# GL3520_4_Ports.net
KiCad netlist of a schematic drawn in Altium Designer
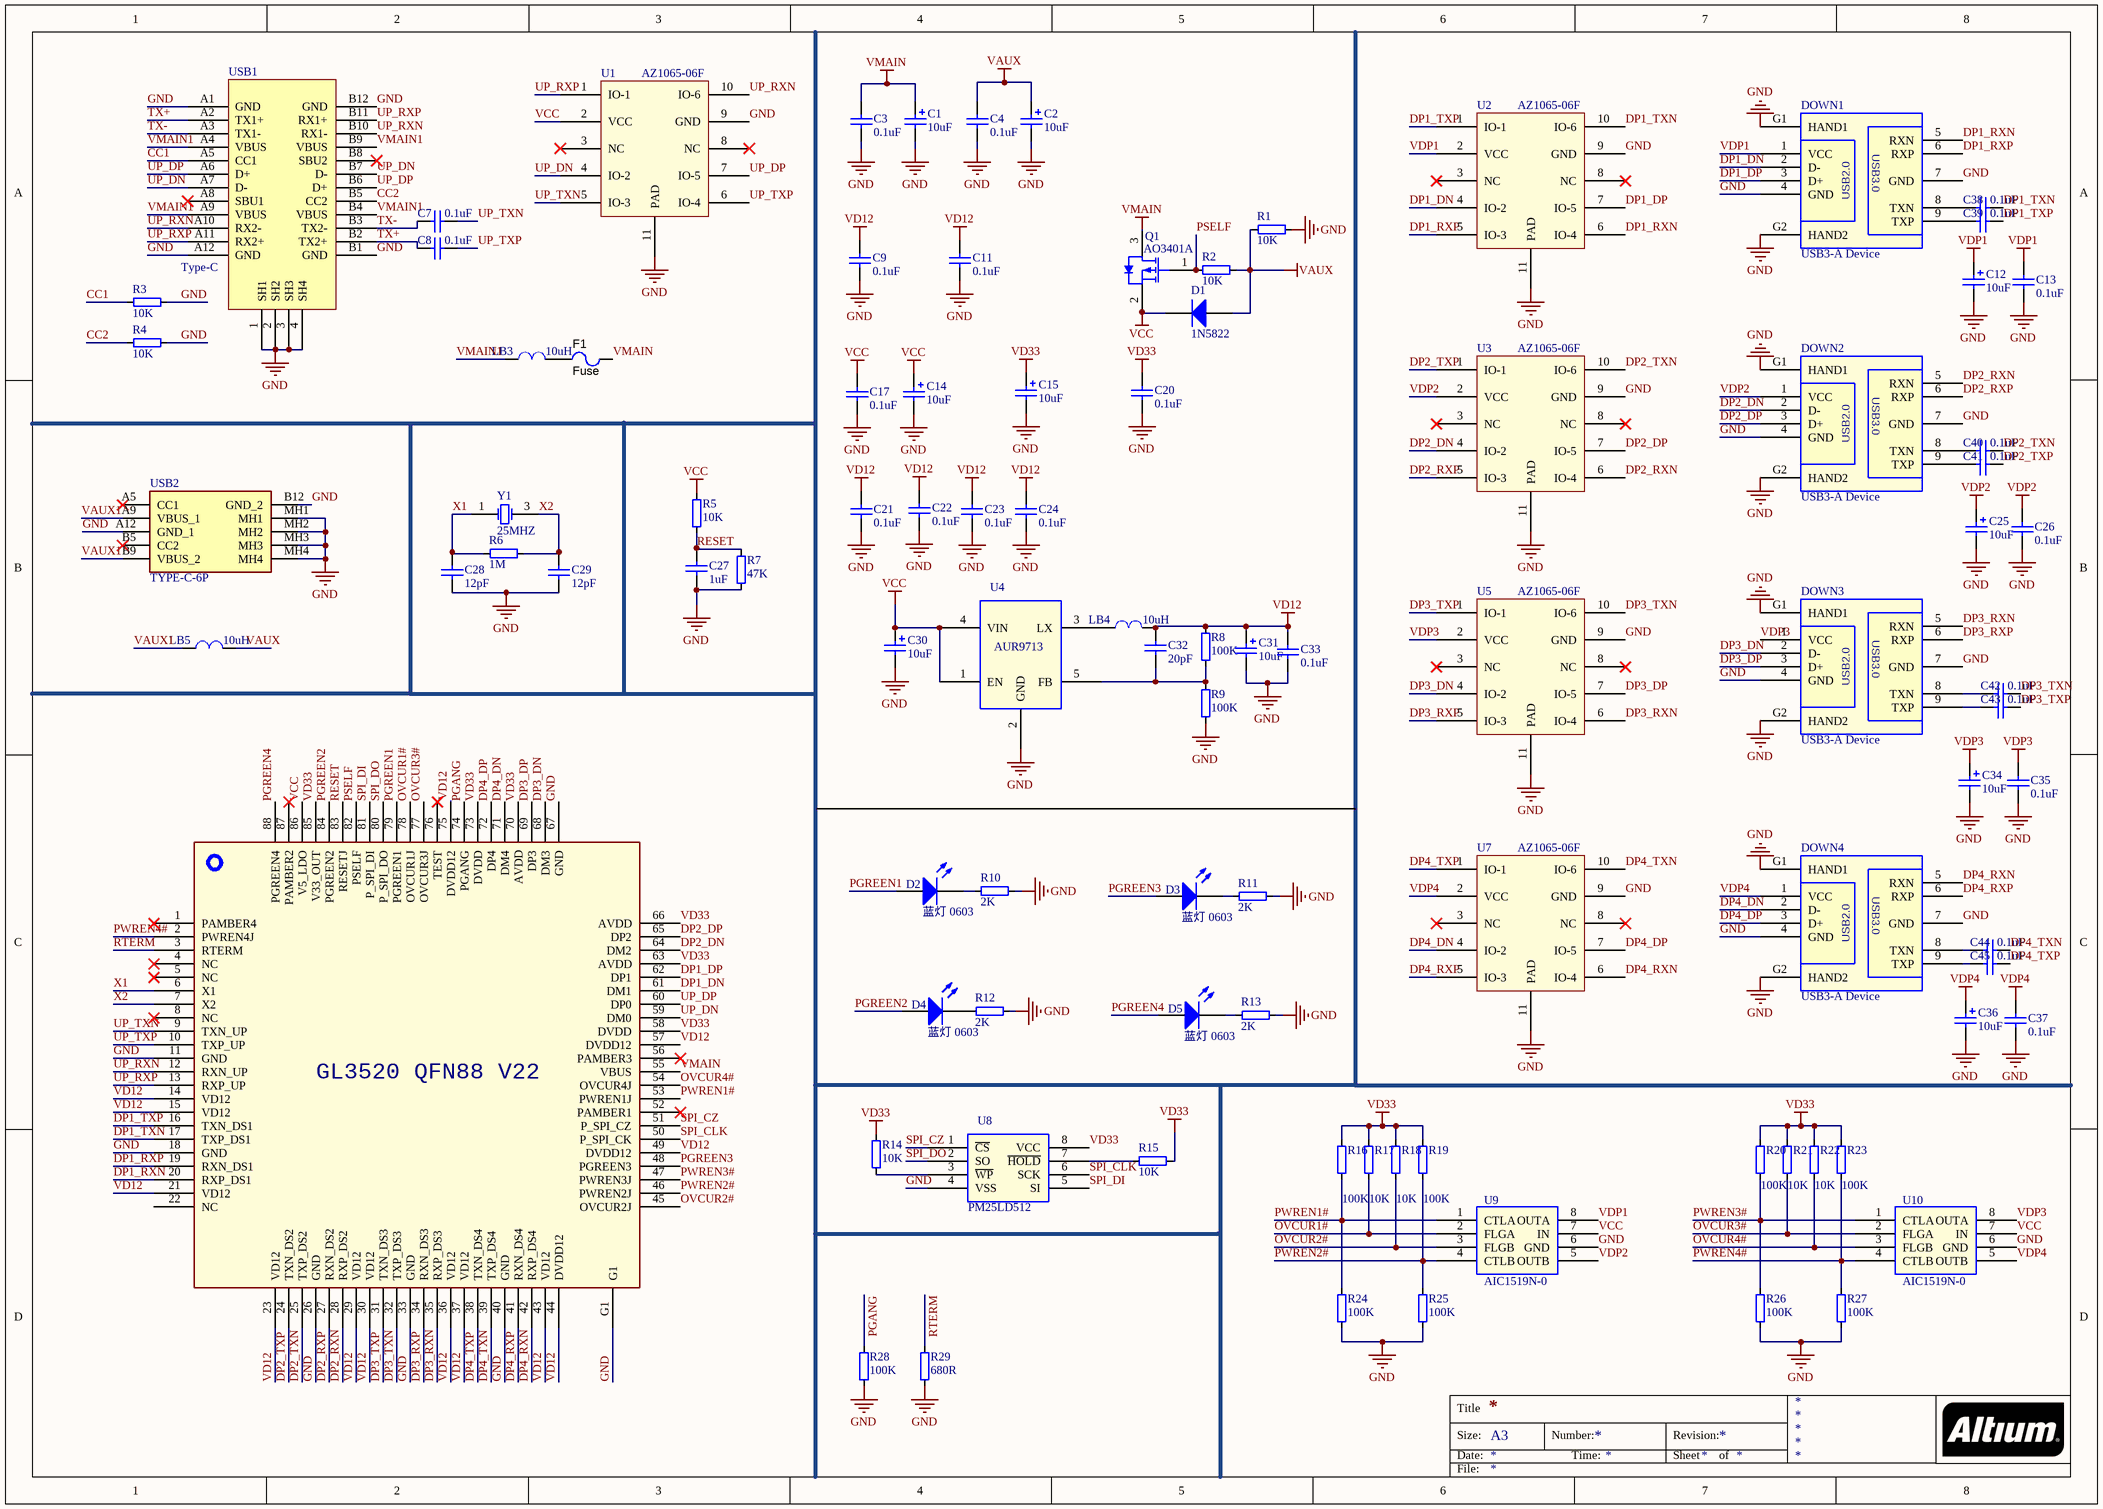
[diagram p0: GL3520 4 Ports.SchDoc]

(export (version "E")
  (design (tool "Eeschema 10.0.6"))
  (components
    (comp (ref "C1")
      (value "10uF")
      (footprint "CASE-A_3216")
      (description "钽电容1206")
      (libsource (lib "嘉立创") (part "3216 10uF (106) 10% 16V"))
    )
    (comp (ref "C2")
      (value "10uF")
      (footprint "CASE-A_3216")
      (description "钽电容1206")
      (libsource (lib "嘉立创") (part "3216 10uF (106) 10% 16V"))
    )
    (comp (ref "C3")
      (value "0.1uF")
      (footprint "C 0603_L")
      (description "贴片电容")
      (libsource (lib "嘉立创") (part "0603 2.2uF (225) 10% 16V"))
    )
    (comp (ref "C4")
      (value "0.1uF")
      (footprint "C 0603_L")
      (description "贴片电容")
      (libsource (lib "嘉立创") (part "0603 2.2uF (225) 10% 16V"))
    )
    (comp (ref "C7")
      (value "0.1uF")
      (footprint "C 0603_L")
      (description "贴片电容")
      (libsource (lib "嘉立创") (part "0603 2.2uF (225) 10% 16V"))
    )
    (comp (ref "C8")
      (value "0.1uF")
      (footprint "C 0603_L")
      (description "贴片电容")
      (libsource (lib "嘉立创") (part "0603 2.2uF (225) 10% 16V"))
    )
    (comp (ref "C9")
      (value "0.1uF")
      (footprint "C 0603_L")
      (description "贴片电容")
      (libsource (lib "嘉立创") (part "0603 2.2uF (225) 10% 16V"))
    )
    (comp (ref "C11")
      (value "0.1uF")
      (footprint "C 0603_L")
      (description "贴片电容")
      (libsource (lib "嘉立创") (part "0603 2.2uF (225) 10% 16V"))
    )
    (comp (ref "C12")
      (value "10uF")
      (footprint "CASE-A_3216")
      (description "钽电容")
      (libsource (lib "嘉立创") (part "3216 10uF (106) 10% 16V"))
    )
    (comp (ref "C13")
      (value "0.1uF")
      (footprint "C 0603_L")
      (description "贴片电容")
      (libsource (lib "嘉立创") (part "0603 2.2uF (225) 10% 16V"))
    )
    (comp (ref "C14")
      (value "10uF")
      (footprint "CASE-A_3216")
      (description "钽电容1206")
      (libsource (lib "嘉立创") (part "3216 10uF (106) 10% 16V"))
    )
    (comp (ref "C15")
      (value "10uF")
      (footprint "CASE-A_3216")
      (description "钽电容1206")
      (libsource (lib "嘉立创") (part "3216 10uF (106) 10% 16V"))
    )
    (comp (ref "C17")
      (value "0.1uF")
      (footprint "C 0603_L")
      (description "贴片电容")
      (libsource (lib "嘉立创") (part "0603 2.2uF (225) 10% 16V"))
    )
    (comp (ref "C20")
      (value "0.1uF")
      (footprint "C 0603_L")
      (description "贴片电容")
      (libsource (lib "嘉立创") (part "0603 2.2uF (225) 10% 16V"))
    )
    (comp (ref "C21")
      (value "0.1uF")
      (footprint "C 0603_L")
      (description "贴片电容")
      (libsource (lib "嘉立创") (part "0603 2.2uF (225) 10% 16V"))
    )
    (comp (ref "C22")
      (value "0.1uF")
      (footprint "C 0603_L")
      (description "贴片电容")
      (libsource (lib "嘉立创") (part "0603 2.2uF (225) 10% 16V"))
    )
    (comp (ref "C23")
      (value "0.1uF")
      (footprint "C 0603_L")
      (description "贴片电容")
      (libsource (lib "嘉立创") (part "0603 2.2uF (225) 10% 16V"))
    )
    (comp (ref "C24")
      (value "0.1uF")
      (footprint "C 0603_L")
      (description "贴片电容")
      (libsource (lib "嘉立创") (part "0603 2.2uF (225) 10% 16V"))
    )
    (comp (ref "C25")
      (value "10uF")
      (footprint "CASE-A_3216")
      (description "钽电容")
      (libsource (lib "嘉立创") (part "3216 10uF (106) 10% 16V"))
    )
    (comp (ref "C26")
      (value "0.1uF")
      (footprint "C 0603_L")
      (description "贴片电容")
      (libsource (lib "嘉立创") (part "0603 2.2uF (225) 10% 16V"))
    )
    (comp (ref "C27")
      (value "1uF")
      (footprint "C 0603_L")
      (description "贴片电容")
      (libsource (lib "嘉立创") (part "0603 2.2uF (225) 10% 16V"))
    )
    (comp (ref "C28")
      (value "12pF")
      (footprint "C 0603_L")
      (description "贴片电容")
      (libsource (lib "嘉立创") (part "0603 2.2uF (225) 10% 16V"))
    )
    (comp (ref "C29")
      (value "12pF")
      (footprint "C 0603_L")
      (description "贴片电容")
      (libsource (lib "嘉立创") (part "0603 2.2uF (225) 10% 16V"))
    )
    (comp (ref "C30")
      (value "10uF")
      (footprint "CASE-A_3216")
      (description "钽电容")
      (libsource (lib "嘉立创") (part "3216 10uF (106) 10% 16V"))
    )
    (comp (ref "C31")
      (value "10uF")
      (footprint "CASE-A_3216")
      (description "钽电容")
      (libsource (lib "嘉立创") (part "3216 10uF (106) 10% 16V"))
    )
    (comp (ref "C32")
      (value "20pF")
      (footprint "C 0603_L")
      (description "贴片电容")
      (libsource (lib "嘉立创") (part "0603 2.2uF (225) 10% 16V"))
    )
    (comp (ref "C33")
      (value "0.1uF")
      (footprint "C 0603_L")
      (description "贴片电容")
      (libsource (lib "嘉立创") (part "0603 2.2uF (225) 10% 16V"))
    )
    (comp (ref "C34")
      (value "10uF")
      (footprint "CASE-A_3216")
      (description "钽电容")
      (libsource (lib "嘉立创") (part "3216 10uF (106) 10% 16V"))
    )
    (comp (ref "C35")
      (value "0.1uF")
      (footprint "C 0603_L")
      (description "贴片电容")
      (libsource (lib "嘉立创") (part "0603 2.2uF (225) 10% 16V"))
    )
    (comp (ref "C36")
      (value "10uF")
      (footprint "CASE-A_3216")
      (description "钽电容")
      (libsource (lib "嘉立创") (part "3216 10uF (106) 10% 16V"))
    )
    (comp (ref "C37")
      (value "0.1uF")
      (footprint "C 0603_L")
      (description "贴片电容")
      (libsource (lib "嘉立创") (part "0603 2.2uF (225) 10% 16V"))
    )
    (comp (ref "C38")
      (value "0.1uF")
      (footprint "C 0603_L")
      (description "贴片电容")
      (libsource (lib "嘉立创") (part "0603 2.2uF (225) 10% 16V"))
    )
    (comp (ref "C39")
      (value "0.1uF")
      (footprint "C 0603_L")
      (description "贴片电容")
      (libsource (lib "嘉立创") (part "0603 2.2uF (225) 10% 16V"))
    )
    (comp (ref "C40")
      (value "0.1uF")
      (footprint "C 0603_L")
      (description "贴片电容")
      (libsource (lib "嘉立创") (part "0603 2.2uF (225) 10% 16V"))
    )
    (comp (ref "C41")
      (value "0.1uF")
      (footprint "C 0603_L")
      (description "贴片电容")
      (libsource (lib "嘉立创") (part "0603 2.2uF (225) 10% 16V"))
    )
    (comp (ref "C42")
      (value "0.1uF")
      (footprint "C 0603_L")
      (description "贴片电容")
      (libsource (lib "嘉立创") (part "0603 2.2uF (225) 10% 16V"))
    )
    (comp (ref "C43")
      (value "0.1uF")
      (footprint "C 0603_L")
      (description "贴片电容")
      (libsource (lib "嘉立创") (part "0603 2.2uF (225) 10% 16V"))
    )
    (comp (ref "C44")
      (value "0.1uF")
      (footprint "C 0603_L")
      (description "贴片电容")
      (libsource (lib "嘉立创") (part "0603 2.2uF (225) 10% 16V"))
    )
    (comp (ref "C45")
      (value "0.1uF")
      (footprint "C 0603_L")
      (description "贴片电容")
      (libsource (lib "嘉立创") (part "0603 2.2uF (225) 10% 16V"))
    )
    (comp (ref "D1")
      (value "1N5822")
      (footprint "SMA")
      (description "3 Amp General Purpose Rectifier")
      (fields (field (name "PUBLISHER") "Altium Limited"))
      (libsource (lib "Miscellaneous Devices") (part "Diode 1N5400"))
    )
    (comp (ref "D2")
      (value "蓝灯 0603")
      (footprint "0603_LED_S1")
      (description "发光二极管")
      (libsource (lib "嘉立创") (part "0603 蓝灯"))
    )
    (comp (ref "D3")
      (value "蓝灯 0603")
      (footprint "0603_LED_S1")
      (description "发光二极管")
      (libsource (lib "嘉立创") (part "0603 蓝灯"))
    )
    (comp (ref "D4")
      (value "蓝灯 0603")
      (footprint "0603_LED_S1")
      (description "发光二极管")
      (libsource (lib "嘉立创") (part "0603 蓝灯"))
    )
    (comp (ref "D5")
      (value "蓝灯 0603")
      (footprint "0603_LED_S1")
      (description "发光二极管")
      (libsource (lib "嘉立创") (part "0603 蓝灯"))
    )
    (comp (ref "DOWN1")
      (value "USB3-A Device")
      (footprint "USB3.0-1 - duplicate")
      (libsource (lib "*") (part "USB3-A_5"))
    )
    (comp (ref "DOWN2")
      (value "USB3-A Device")
      (footprint "USB3.0-1 - duplicate")
      (libsource (lib "*") (part "USB3-A_5"))
    )
    (comp (ref "DOWN3")
      (value "USB3-A Device")
      (footprint "USB3.0-1 - duplicate")
      (libsource (lib "*") (part "USB3-A_5"))
    )
    (comp (ref "DOWN4")
      (value "USB3-A Device")
      (footprint "USB3.0-1 - duplicate")
      (libsource (lib "*") (part "USB3-A_5"))
    )
    (comp (ref "F1")
      (value "Fuse")
      (footprint "FU 1206")
      (fields
        (field (name "PARTNUMBER") "NANOSMDC020F-2")
        (field (name "MANUFACTURER") "TE Connectivity")
        (field (name "PUBLISHER") "Texas Instruments")
        (field (name "SYMBOLCREATOR") "a0412235")
      )
      (libsource (lib "TUSB8041_USB_3.0_Hub") (part "Fuse"))
    )
    (comp (ref "LB3") (value "10uH") (footprint "CD43") (libsource (lib "*") (part "L-0603")))
    (comp (ref "LB4") (value "10uH") (footprint "CD43") (libsource (lib "*") (part "L-0603")))
    (comp (ref "LB5") (value "10uH") (footprint "CD43") (libsource (lib "*") (part "L-0603")))
    (comp (ref "Q1")
      (value "AO3401A")
      (footprint "SOT23-3L")
      (description "P-Channel MOSFET, 30 V, 4 A, -55 to 150 degC, 3-Pin SOT-23-3L, RoHS, Tape and Reel")
      (fields (field (name "MANUFACTURER") "Alpha and Omega"))
      (libsource (lib "GL3520 4 Ports") (part "CMP-2000-05778-1"))
    )
    (comp (ref "R1") (value "10K") (footprint "R 0603_L") (libsource (lib "Jlink OB") (part "RES")))
    (comp (ref "R2") (value "10K") (footprint "R 0603_L") (libsource (lib "Jlink OB") (part "RES")))
    (comp (ref "R3") (value "10K") (footprint "R 0603_L") (libsource (lib "Jlink OB") (part "RES")))
    (comp (ref "R4") (value "10K") (footprint "R 0603_L") (libsource (lib "Jlink OB") (part "RES")))
    (comp (ref "R5") (value "10K") (footprint "R 0603_L") (libsource (lib "Jlink OB") (part "RES")))
    (comp (ref "R6") (value "1M") (footprint "R 0603_L") (libsource (lib "Jlink OB") (part "RES")))
    (comp (ref "R7") (value "47K") (footprint "R 0603_L") (libsource (lib "Jlink OB") (part "RES")))
    (comp (ref "R8") (value "100K") (footprint "R 0603_L") (libsource (lib "Jlink OB") (part "RES")))
    (comp (ref "R9") (value "100K") (footprint "R 0603_L") (libsource (lib "Jlink OB") (part "RES")))
    (comp (ref "R10") (value "2K") (footprint "R 0603_L") (libsource (lib "Jlink OB") (part "RES")))
    (comp (ref "R11") (value "2K") (footprint "R 0603_L") (libsource (lib "Jlink OB") (part "RES")))
    (comp (ref "R12") (value "2K") (footprint "R 0603_L") (libsource (lib "Jlink OB") (part "RES")))
    (comp (ref "R13") (value "2K") (footprint "R 0603_L") (libsource (lib "Jlink OB") (part "RES")))
    (comp (ref "R14") (value "10K") (footprint "R 0603_L") (libsource (lib "Jlink OB") (part "RES")))
    (comp (ref "R15") (value "10K") (footprint "R 0603_L") (libsource (lib "Jlink OB") (part "RES")))
    (comp (ref "R16") (value "100K") (footprint "R 0603_L") (libsource (lib "Jlink OB") (part "RES")))
    (comp (ref "R17") (value "10K") (footprint "R 0603_L") (libsource (lib "Jlink OB") (part "RES")))
    (comp (ref "R18") (value "10K") (footprint "R 0603_L") (libsource (lib "Jlink OB") (part "RES")))
    (comp (ref "R19") (value "100K") (footprint "R 0603_L") (libsource (lib "Jlink OB") (part "RES")))
    (comp (ref "R20") (value "100K") (footprint "R 0603_L") (libsource (lib "Jlink OB") (part "RES")))
    (comp (ref "R21") (value "10K") (footprint "R 0603_L") (libsource (lib "Jlink OB") (part "RES")))
    (comp (ref "R22") (value "10K") (footprint "R 0603_L") (libsource (lib "Jlink OB") (part "RES")))
    (comp (ref "R23") (value "100K") (footprint "R 0603_L") (libsource (lib "Jlink OB") (part "RES")))
    (comp (ref "R24") (value "100K") (footprint "R 0603_L") (libsource (lib "Jlink OB") (part "RES")))
    (comp (ref "R25") (value "100K") (footprint "R 0603_L") (libsource (lib "Jlink OB") (part "RES")))
    (comp (ref "R26") (value "100K") (footprint "R 0603_L") (libsource (lib "Jlink OB") (part "RES")))
    (comp (ref "R27") (value "100K") (footprint "R 0603_L") (libsource (lib "Jlink OB") (part "RES")))
    (comp (ref "R28") (value "100K") (footprint "R 0603_L") (libsource (lib "Jlink OB") (part "RES")))
    (comp (ref "R29") (value "680R") (footprint "R 0603_L") (libsource (lib "Jlink OB") (part "RES")))
    (comp (ref "U1")
      (value "AZ1065-06F")
      (footprint "DFN4120P10E")
      (description "晶炎AZ1065-06F.R7G DFN4120 丝印119 ESD/TVS静电保护二极管")
      (libsource (lib "GL3520 4 Ports") (part "AZ1065-06F"))
    )
    (comp (ref "U2")
      (value "AZ1065-06F")
      (footprint "DFN4120P10E")
      (description "晶炎AZ1065-06F.R7G DFN4120 丝印119 ESD/TVS静电保护二极管")
      (libsource (lib "GL3520 4 Ports") (part "AZ1065-06F"))
    )
    (comp (ref "U3")
      (value "AZ1065-06F")
      (footprint "DFN4120P10E")
      (description "晶炎AZ1065-06F.R7G DFN4120 丝印119 ESD/TVS静电保护二极管")
      (libsource (lib "GL3520 4 Ports") (part "AZ1065-06F"))
    )
    (comp (ref "U4") (value "AUR9713") (footprint "SOT23-5L") (libsource (lib "*") (part "AUR9705_3")))
    (comp (ref "U5")
      (value "AZ1065-06F")
      (footprint "DFN4120P10E")
      (description "晶炎AZ1065-06F.R7G DFN4120 丝印119 ESD/TVS静电保护二极管")
      (libsource (lib "GL3520 4 Ports") (part "AZ1065-06F"))
    )
    (comp (ref "U6")
      (value "GL3520_QFN88_V094-1_22")
      (footprint "QFN88")
      (libsource (lib "GL3520 4 Ports") (part "GL3520_QFN88_V094-1_22"))
    )
    (comp (ref "U7")
      (value "AZ1065-06F")
      (footprint "DFN4120P10E")
      (description "晶炎AZ1065-06F.R7G DFN4120 丝印119 ESD/TVS静电保护二极管")
      (libsource (lib "GL3520 4 Ports") (part "AZ1065-06F"))
    )
    (comp (ref "U8") (value "PM25LD512") (footprint "SOP8W_M") (libsource (lib "*") (part "CAT25C128/256")))
    (comp (ref "U9") (value "AIC1519N-0") (footprint "SOP8_L") (libsource (lib "*") (part "AIC1526-SOP")))
    (comp (ref "U10") (value "AIC1519N-0") (footprint "SOP8_L") (libsource (lib "*") (part "AIC1526-SOP")))
    (comp (ref "USB1")
      (value "Type-C")
      (footprint "USB_TYPE_C_24P - duplicate - duplicate")
      (libsource (lib "Jlink OB") (part "Type-C"))
    )
    (comp (ref "USB2")
      (value "TYPE-C-6P")
      (footprint "USB_TYPE_C_6P")
      (description "Connector")
      (fields (field (name "MANUFACTURER_PART_NUMBER") "TYPE-C-31-M-17"))
      (libsource (lib "SamacSys") (part "TYPE-C-31-M-17"))
    )
    (comp (ref "Y1")
      (value "25MHZ")
      (footprint "OSC 3225-4P")
      (description "贴片晶振")
      (libsource (lib "嘉立创") (part "SMD-3225_4P  25MHZ 12PF 10PPM"))
    )
  )
  (nets
    (net (code "1") (name "/CC1") (class "Default")
      (node (ref "R3") (pin "1") (pinfunction "1_1") (pintype "passive"))
      (node (ref "USB1") (pin "A5") (pinfunction "CC1_A5") (pintype "passive"))
    )
    (net (code "2") (name "/CC2") (class "Default")
      (node (ref "R4") (pin "1") (pinfunction "1_1") (pintype "passive"))
      (node (ref "USB1") (pin "B5") (pinfunction "CC2_B5") (pintype "passive"))
    )
    (net (code "3") (name "/DP1_DN") (class "Default")
      (node (ref "DOWN1") (pin "2") (pinfunction "D-_2") (pintype "passive"))
      (node (ref "U2") (pin "4") (pinfunction "IO-2_4") (pintype "passive"))
      (node (ref "U6") (pin "61") (pinfunction "DM1_61") (pintype "passive"))
    )
    (net (code "4") (name "/DP1_DP") (class "Default")
      (node (ref "DOWN1") (pin "3") (pinfunction "D+_3") (pintype "passive"))
      (node (ref "U2") (pin "7") (pinfunction "IO-5_7") (pintype "passive"))
      (node (ref "U6") (pin "62") (pinfunction "DP1_62") (pintype "passive"))
    )
    (net (code "5") (name "/DP1_RXN") (class "Default")
      (node (ref "DOWN1") (pin "5") (pinfunction "RXN_5") (pintype "passive"))
      (node (ref "U2") (pin "6") (pinfunction "IO-4_6") (pintype "passive"))
      (node (ref "U6") (pin "20") (pinfunction "RXP_DS1_20") (pintype "passive"))
    )
    (net (code "6") (name "/DP1_RXP") (class "Default")
      (node (ref "DOWN1") (pin "6") (pinfunction "RXP_6") (pintype "passive"))
      (node (ref "U2") (pin "5") (pinfunction "IO-3_5") (pintype "passive"))
      (node (ref "U6") (pin "19") (pinfunction "RXN_DS1_19") (pintype "passive"))
    )
    (net (code "7") (name "/DP1_TXN") (class "Default")
      (node (ref "C38") (pin "1") (pinfunction "1_1") (pintype "passive"))
      (node (ref "U2") (pin "10") (pinfunction "IO-6_10") (pintype "passive"))
      (node (ref "U6") (pin "17") (pinfunction "TXP_DS1_17") (pintype "passive"))
    )
    (net (code "8") (name "/DP1_TXP") (class "Default")
      (node (ref "C39") (pin "1") (pinfunction "1_1") (pintype "passive"))
      (node (ref "U2") (pin "1") (pinfunction "IO-1_1") (pintype "passive"))
      (node (ref "U6") (pin "16") (pinfunction "TXN_DS1_16") (pintype "passive"))
    )
    (net (code "9") (name "/DP2_DN") (class "Default")
      (node (ref "DOWN2") (pin "2") (pinfunction "D-_2") (pintype "passive"))
      (node (ref "U3") (pin "4") (pinfunction "IO-2_4") (pintype "passive"))
      (node (ref "U6") (pin "64") (pinfunction "DM2_64") (pintype "passive"))
    )
    (net (code "10") (name "/DP2_DP") (class "Default")
      (node (ref "DOWN2") (pin "3") (pinfunction "D+_3") (pintype "passive"))
      (node (ref "U3") (pin "7") (pinfunction "IO-5_7") (pintype "passive"))
      (node (ref "U6") (pin "65") (pinfunction "DP2_65") (pintype "passive"))
    )
    (net (code "11") (name "/DP2_RXN") (class "Default")
      (node (ref "DOWN2") (pin "5") (pinfunction "RXN_5") (pintype "passive"))
      (node (ref "U3") (pin "6") (pinfunction "IO-4_6") (pintype "passive"))
      (node (ref "U6") (pin "28") (pinfunction "RXP_DS2_28") (pintype "passive"))
    )
    (net (code "12") (name "/DP2_RXP") (class "Default")
      (node (ref "DOWN2") (pin "6") (pinfunction "RXP_6") (pintype "passive"))
      (node (ref "U3") (pin "5") (pinfunction "IO-3_5") (pintype "passive"))
      (node (ref "U6") (pin "27") (pinfunction "RXN_DS2_27") (pintype "passive"))
    )
    (net (code "13") (name "/DP2_TXN") (class "Default")
      (node (ref "C40") (pin "1") (pinfunction "1_1") (pintype "passive"))
      (node (ref "U3") (pin "10") (pinfunction "IO-6_10") (pintype "passive"))
      (node (ref "U6") (pin "25") (pinfunction "TXP_DS2_25") (pintype "passive"))
    )
    (net (code "14") (name "/DP2_TXP") (class "Default")
      (node (ref "C41") (pin "1") (pinfunction "1_1") (pintype "passive"))
      (node (ref "U3") (pin "1") (pinfunction "IO-1_1") (pintype "passive"))
      (node (ref "U6") (pin "24") (pinfunction "TXN_DS2_24") (pintype "passive"))
    )
    (net (code "15") (name "/DP3_DN") (class "Default")
      (node (ref "DOWN3") (pin "2") (pinfunction "D-_2") (pintype "passive"))
      (node (ref "U5") (pin "4") (pinfunction "IO-2_4") (pintype "passive"))
      (node (ref "U6") (pin "68") (pinfunction "DM3_68") (pintype "passive"))
    )
    (net (code "16") (name "/DP3_DP") (class "Default")
      (node (ref "DOWN3") (pin "3") (pinfunction "D+_3") (pintype "passive"))
      (node (ref "U5") (pin "7") (pinfunction "IO-5_7") (pintype "passive"))
      (node (ref "U6") (pin "69") (pinfunction "DP3_69") (pintype "passive"))
    )
    (net (code "17") (name "/DP3_RXN") (class "Default")
      (node (ref "DOWN3") (pin "5") (pinfunction "RXN_5") (pintype "passive"))
      (node (ref "U5") (pin "6") (pinfunction "IO-4_6") (pintype "passive"))
      (node (ref "U6") (pin "35") (pinfunction "RXP_DS3_35") (pintype "passive"))
    )
    (net (code "18") (name "/DP3_RXP") (class "Default")
      (node (ref "DOWN3") (pin "6") (pinfunction "RXP_6") (pintype "passive"))
      (node (ref "U5") (pin "5") (pinfunction "IO-3_5") (pintype "passive"))
      (node (ref "U6") (pin "34") (pinfunction "RXN_DS3_34") (pintype "passive"))
    )
    (net (code "19") (name "/DP3_TXN") (class "Default")
      (node (ref "C42") (pin "1") (pinfunction "1_1") (pintype "passive"))
      (node (ref "U5") (pin "10") (pinfunction "IO-6_10") (pintype "passive"))
      (node (ref "U6") (pin "32") (pinfunction "TXP_DS3_32") (pintype "passive"))
    )
    (net (code "20") (name "/DP3_TXP") (class "Default")
      (node (ref "C43") (pin "1") (pinfunction "1_1") (pintype "passive"))
      (node (ref "U5") (pin "1") (pinfunction "IO-1_1") (pintype "passive"))
      (node (ref "U6") (pin "31") (pinfunction "TXN_DS3_31") (pintype "passive"))
    )
    (net (code "21") (name "/DP4_DN") (class "Default")
      (node (ref "DOWN4") (pin "2") (pinfunction "D-_2") (pintype "passive"))
      (node (ref "U6") (pin "71") (pinfunction "DM4_71") (pintype "passive"))
      (node (ref "U7") (pin "4") (pinfunction "IO-2_4") (pintype "passive"))
    )
    (net (code "22") (name "/DP4_DP") (class "Default")
      (node (ref "DOWN4") (pin "3") (pinfunction "D+_3") (pintype "passive"))
      (node (ref "U6") (pin "72") (pinfunction "DP4_72") (pintype "passive"))
      (node (ref "U7") (pin "7") (pinfunction "IO-5_7") (pintype "passive"))
    )
    (net (code "23") (name "/DP4_RXN") (class "Default")
      (node (ref "DOWN4") (pin "5") (pinfunction "RXN_5") (pintype "passive"))
      (node (ref "U6") (pin "42") (pinfunction "RXP_DS4_42") (pintype "passive"))
      (node (ref "U7") (pin "6") (pinfunction "IO-4_6") (pintype "passive"))
    )
    (net (code "24") (name "/DP4_RXP") (class "Default")
      (node (ref "DOWN4") (pin "6") (pinfunction "RXP_6") (pintype "passive"))
      (node (ref "U6") (pin "41") (pinfunction "RXN_DS4_41") (pintype "passive"))
      (node (ref "U7") (pin "5") (pinfunction "IO-3_5") (pintype "passive"))
    )
    (net (code "25") (name "/DP4_TXN") (class "Default")
      (node (ref "C44") (pin "1") (pinfunction "1_1") (pintype "passive"))
      (node (ref "U6") (pin "39") (pinfunction "TXP_DS4_39") (pintype "passive"))
      (node (ref "U7") (pin "10") (pinfunction "IO-6_10") (pintype "passive"))
    )
    (net (code "26") (name "/DP4_TXP") (class "Default")
      (node (ref "C45") (pin "1") (pinfunction "1_1") (pintype "passive"))
      (node (ref "U6") (pin "38") (pinfunction "TXN_DS4_38") (pintype "passive"))
      (node (ref "U7") (pin "1") (pinfunction "IO-1_1") (pintype "passive"))
    )
    (net (code "27") (name "/OVCUR1#") (class "Default")
      (node (ref "R17") (pin "2") (pinfunction "2_2") (pintype "passive"))
      (node (ref "U6") (pin "78") (pinfunction "OVCUR1J_78") (pintype "passive"))
      (node (ref "U9") (pin "2") (pinfunction "FLGA_2") (pintype "passive"))
    )
    (net (code "28") (name "/OVCUR2#") (class "Default")
      (node (ref "R18") (pin "2") (pinfunction "2_2") (pintype "passive"))
      (node (ref "U6") (pin "45") (pinfunction "OVCUR2J_45") (pintype "passive"))
      (node (ref "U9") (pin "3") (pinfunction "FLGB_3") (pintype "passive"))
    )
    (net (code "29") (name "/OVCUR3#") (class "Default")
      (node (ref "R21") (pin "2") (pinfunction "2_2") (pintype "passive"))
      (node (ref "U10") (pin "2") (pinfunction "FLGA_2") (pintype "passive"))
      (node (ref "U6") (pin "77") (pinfunction "OVCUR3J_77") (pintype "passive"))
    )
    (net (code "30") (name "/OVCUR4#") (class "Default")
      (node (ref "R22") (pin "2") (pinfunction "2_2") (pintype "passive"))
      (node (ref "U10") (pin "3") (pinfunction "FLGB_3") (pintype "passive"))
      (node (ref "U6") (pin "54") (pinfunction "OVCUR4J_54") (pintype "passive"))
    )
    (net (code "31") (name "/PGANG") (class "Default")
      (node (ref "R28") (pin "1") (pinfunction "1_1") (pintype "passive"))
      (node (ref "U6") (pin "74") (pinfunction "PGANG_74") (pintype "passive"))
    )
    (net (code "32") (name "/PGREEN1") (class "Default")
      (node (ref "D2") (pin "A") (pinfunction "A_A") (pintype "passive"))
      (node (ref "U6") (pin "79") (pinfunction "PGREEN1_79") (pintype "passive"))
    )
    (net (code "33") (name "/PGREEN2") (class "Default")
      (node (ref "D4") (pin "A") (pinfunction "A_A") (pintype "passive"))
      (node (ref "U6") (pin "84") (pinfunction "PGREEN2_84") (pintype "passive"))
    )
    (net (code "34") (name "/PGREEN3") (class "Default")
      (node (ref "D3") (pin "A") (pinfunction "A_A") (pintype "passive"))
      (node (ref "U6") (pin "48") (pinfunction "PGREEN3_48") (pintype "passive"))
    )
    (net (code "35") (name "/PGREEN4") (class "Default")
      (node (ref "D5") (pin "A") (pinfunction "A_A") (pintype "passive"))
      (node (ref "U6") (pin "88") (pinfunction "PGREEN4_88") (pintype "passive"))
    )
    (net (code "36") (name "/PSELF") (class "Default")
      (node (ref "Q1") (pin "1") (pinfunction "GATE_1") (pintype "passive"))
      (node (ref "R2") (pin "1") (pinfunction "1_1") (pintype "passive"))
      (node (ref "U6") (pin "82") (pinfunction "PSELF_82") (pintype "passive"))
    )
    (net (code "37") (name "/PWREN1#") (class "Default")
      (node (ref "R16") (pin "2") (pinfunction "2_2") (pintype "passive"))
      (node (ref "R24") (pin "1") (pinfunction "1_1") (pintype "passive"))
      (node (ref "U6") (pin "53") (pinfunction "PWREN1J_53") (pintype "passive"))
      (node (ref "U9") (pin "1") (pinfunction "CTLA_1") (pintype "passive"))
    )
    (net (code "38") (name "/PWREN2#") (class "Default")
      (node (ref "R19") (pin "2") (pinfunction "2_2") (pintype "passive"))
      (node (ref "R25") (pin "1") (pinfunction "1_1") (pintype "passive"))
      (node (ref "U6") (pin "46") (pinfunction "PWREN2J_46") (pintype "passive"))
      (node (ref "U9") (pin "4") (pinfunction "CTLB_4") (pintype "passive"))
    )
    (net (code "39") (name "/PWREN3#") (class "Default")
      (node (ref "R20") (pin "2") (pinfunction "2_2") (pintype "passive"))
      (node (ref "R26") (pin "1") (pinfunction "1_1") (pintype "passive"))
      (node (ref "U10") (pin "1") (pinfunction "CTLA_1") (pintype "passive"))
      (node (ref "U6") (pin "47") (pinfunction "PWREN3J_47") (pintype "passive"))
    )
    (net (code "40") (name "/PWREN4#") (class "Default")
      (node (ref "R23") (pin "2") (pinfunction "2_2") (pintype "passive"))
      (node (ref "R27") (pin "1") (pinfunction "1_1") (pintype "passive"))
      (node (ref "U10") (pin "4") (pinfunction "CTLB_4") (pintype "passive"))
      (node (ref "U6") (pin "2") (pinfunction "PWREN4J_2") (pintype "passive"))
    )
    (net (code "41") (name "/RESET") (class "Default")
      (node (ref "C27") (pin "2") (pinfunction "2_2") (pintype "passive"))
      (node (ref "R5") (pin "1") (pinfunction "1_1") (pintype "passive"))
      (node (ref "R7") (pin "2") (pinfunction "2_2") (pintype "passive"))
      (node (ref "U6") (pin "83") (pinfunction "RESETJ_83") (pintype "passive"))
    )
    (net (code "42") (name "/RTERM") (class "Default")
      (node (ref "R29") (pin "1") (pinfunction "1_1") (pintype "passive"))
      (node (ref "U6") (pin "3") (pinfunction "RTERM_3") (pintype "passive"))
    )
    (net (code "43") (name "/SPI_CLK") (class "Default")
      (node (ref "U6") (pin "50") (pinfunction "P_SPI_CK_50") (pintype "passive"))
      (node (ref "U8") (pin "6") (pinfunction "SCK_6") (pintype "passive"))
    )
    (net (code "44") (name "/SPI_CZ") (class "Default")
      (node (ref "U6") (pin "51") (pinfunction "P_SPI_CZ_51") (pintype "passive"))
      (node (ref "U8") (pin "1") (pinfunction "~{CS}_1") (pintype "passive"))
    )
    (net (code "45") (name "/SPI_DI") (class "Default")
      (node (ref "U6") (pin "81") (pinfunction "P_SPI_DI_81") (pintype "passive"))
      (node (ref "U8") (pin "5") (pinfunction "SI_5") (pintype "passive"))
    )
    (net (code "46") (name "/SPI_DO") (class "Default")
      (node (ref "U6") (pin "80") (pinfunction "P_SPI_DO_80") (pintype "passive"))
      (node (ref "U8") (pin "2") (pinfunction "SO_2") (pintype "passive"))
    )
    (net (code "47") (name "/TX+") (class "Default")
      (node (ref "C8") (pin "2") (pinfunction "2_2") (pintype "passive"))
      (node (ref "USB1") (pin "A2") (pinfunction "TX1+_A2") (pintype "passive"))
      (node (ref "USB1") (pin "B2") (pinfunction "TX2+_B2") (pintype "passive"))
    )
    (net (code "48") (name "/TX-") (class "Default")
      (node (ref "C7") (pin "2") (pinfunction "2_2") (pintype "passive"))
      (node (ref "USB1") (pin "A3") (pinfunction "TX1-_A3") (pintype "passive"))
      (node (ref "USB1") (pin "B3") (pinfunction "TX2-_B3") (pintype "passive"))
    )
    (net (code "49") (name "/UP_DN") (class "Default")
      (node (ref "U1") (pin "4") (pinfunction "IO-2_4") (pintype "passive"))
      (node (ref "U6") (pin "59") (pinfunction "DM0_59") (pintype "passive"))
      (node (ref "USB1") (pin "A7") (pinfunction "D-_A7") (pintype "passive"))
      (node (ref "USB1") (pin "B7") (pinfunction "D-_B7") (pintype "passive"))
    )
    (net (code "50") (name "/UP_DP") (class "Default")
      (node (ref "U1") (pin "7") (pinfunction "IO-5_7") (pintype "passive"))
      (node (ref "U6") (pin "60") (pinfunction "DP0_60") (pintype "passive"))
      (node (ref "USB1") (pin "A6") (pinfunction "D+_A6") (pintype "passive"))
      (node (ref "USB1") (pin "B6") (pinfunction "D+_B6") (pintype "passive"))
    )
    (net (code "51") (name "/UP_RXN") (class "Default")
      (node (ref "U1") (pin "10") (pinfunction "IO-6_10") (pintype "passive"))
      (node (ref "U6") (pin "12") (pinfunction "RXN_UP_12") (pintype "passive"))
      (node (ref "USB1") (pin "A10") (pinfunction "RX2-_A10") (pintype "passive"))
      (node (ref "USB1") (pin "B10") (pinfunction "RX1-_B10") (pintype "passive"))
    )
    (net (code "52") (name "/UP_RXP") (class "Default")
      (node (ref "U1") (pin "1") (pinfunction "IO-1_1") (pintype "passive"))
      (node (ref "U6") (pin "13") (pinfunction "RXP_UP_13") (pintype "passive"))
      (node (ref "USB1") (pin "A11") (pinfunction "RX2+_A11") (pintype "passive"))
      (node (ref "USB1") (pin "B11") (pinfunction "RX1+_B11") (pintype "passive"))
    )
    (net (code "53") (name "/UP_TXN") (class "Default")
      (node (ref "C7") (pin "1") (pinfunction "1_1") (pintype "passive"))
      (node (ref "U1") (pin "5") (pinfunction "IO-3_5") (pintype "passive"))
      (node (ref "U6") (pin "9") (pinfunction "TXN_UP_9") (pintype "passive"))
    )
    (net (code "54") (name "/UP_TXP") (class "Default")
      (node (ref "C8") (pin "1") (pinfunction "1_1") (pintype "passive"))
      (node (ref "U1") (pin "6") (pinfunction "IO-4_6") (pintype "passive"))
      (node (ref "U6") (pin "10") (pinfunction "TXP_UP_10") (pintype "passive"))
    )
    (net (code "55") (name "/VAUX1") (class "Default")
      (node (ref "LB5") (pin "1") (pinfunction "1_1") (pintype "passive"))
      (node (ref "USB2") (pin "A9") (pinfunction "VBUS_1_A9") (pintype "passive"))
      (node (ref "USB2") (pin "B9") (pinfunction "VBUS_2_B9") (pintype "passive"))
    )
    (net (code "56") (name "/VMAIN1") (class "Default")
      (node (ref "LB3") (pin "1") (pinfunction "1_1") (pintype "passive"))
      (node (ref "USB1") (pin "A4") (pinfunction "VBUS_A4") (pintype "passive"))
      (node (ref "USB1") (pin "A9") (pinfunction "VBUS_A9") (pintype "passive"))
      (node (ref "USB1") (pin "B4") (pinfunction "VBUS_B4") (pintype "passive"))
      (node (ref "USB1") (pin "B9") (pinfunction "VBUS_B9") (pintype "passive"))
    )
    (net (code "57") (name "/X1") (class "Default")
      (node (ref "C28") (pin "2") (pinfunction "2_2") (pintype "passive"))
      (node (ref "R6") (pin "1") (pinfunction "1_1") (pintype "passive"))
      (node (ref "U6") (pin "6") (pinfunction "X1_6") (pintype "passive"))
      (node (ref "Y1") (pin "1") (pinfunction "OSC1_1") (pintype "passive"))
    )
    (net (code "58") (name "/X2") (class "Default")
      (node (ref "C29") (pin "2") (pinfunction "2_2") (pintype "passive"))
      (node (ref "R6") (pin "2") (pinfunction "2_2") (pintype "passive"))
      (node (ref "U6") (pin "7") (pinfunction "X2_7") (pintype "passive"))
      (node (ref "Y1") (pin "3") (pinfunction "OSC2_3") (pintype "passive"))
    )
    (net (code "59") (name "GND") (class "Default")
      (node (ref "C1") (pin "2") (pinfunction "2_2") (pintype "passive"))
      (node (ref "C11") (pin "1") (pinfunction "1_1") (pintype "passive"))
      (node (ref "C12") (pin "2") (pinfunction "2_2") (pintype "passive"))
      (node (ref "C13") (pin "1") (pinfunction "1_1") (pintype "passive"))
      (node (ref "C14") (pin "2") (pinfunction "2_2") (pintype "passive"))
      (node (ref "C15") (pin "2") (pinfunction "2_2") (pintype "passive"))
      (node (ref "C17") (pin "1") (pinfunction "1_1") (pintype "passive"))
      (node (ref "C2") (pin "2") (pinfunction "2_2") (pintype "passive"))
      (node (ref "C20") (pin "1") (pinfunction "1_1") (pintype "passive"))
      (node (ref "C21") (pin "1") (pinfunction "1_1") (pintype "passive"))
      (node (ref "C22") (pin "1") (pinfunction "1_1") (pintype "passive"))
      (node (ref "C23") (pin "1") (pinfunction "1_1") (pintype "passive"))
      (node (ref "C24") (pin "1") (pinfunction "1_1") (pintype "passive"))
      (node (ref "C25") (pin "2") (pinfunction "2_2") (pintype "passive"))
      (node (ref "C26") (pin "1") (pinfunction "1_1") (pintype "passive"))
      (node (ref "C27") (pin "1") (pinfunction "1_1") (pintype "passive"))
      (node (ref "C28") (pin "1") (pinfunction "1_1") (pintype "passive"))
      (node (ref "C29") (pin "1") (pinfunction "1_1") (pintype "passive"))
      (node (ref "C3") (pin "1") (pinfunction "1_1") (pintype "passive"))
      (node (ref "C30") (pin "2") (pinfunction "2_2") (pintype "passive"))
      (node (ref "C31") (pin "2") (pinfunction "2_2") (pintype "passive"))
      (node (ref "C33") (pin "1") (pinfunction "1_1") (pintype "passive"))
      (node (ref "C34") (pin "2") (pinfunction "2_2") (pintype "passive"))
      (node (ref "C35") (pin "1") (pinfunction "1_1") (pintype "passive"))
      (node (ref "C36") (pin "2") (pinfunction "2_2") (pintype "passive"))
      (node (ref "C37") (pin "1") (pinfunction "1_1") (pintype "passive"))
      (node (ref "C4") (pin "1") (pinfunction "1_1") (pintype "passive"))
      (node (ref "C9") (pin "1") (pinfunction "1_1") (pintype "passive"))
      (node (ref "DOWN1") (pin "4") (pinfunction "GND_4") (pintype "power_in"))
      (node (ref "DOWN1") (pin "7") (pinfunction "GND_7") (pintype "power_in"))
      (node (ref "DOWN1") (pin "G1") (pinfunction "HAND1_G1") (pintype "passive"))
      (node (ref "DOWN1") (pin "G2") (pinfunction "HAND2_G2") (pintype "passive"))
      (node (ref "DOWN2") (pin "4") (pinfunction "GND_4") (pintype "power_in"))
      (node (ref "DOWN2") (pin "7") (pinfunction "GND_7") (pintype "power_in"))
      (node (ref "DOWN2") (pin "G1") (pinfunction "HAND1_G1") (pintype "passive"))
      (node (ref "DOWN2") (pin "G2") (pinfunction "HAND2_G2") (pintype "passive"))
      (node (ref "DOWN3") (pin "4") (pinfunction "GND_4") (pintype "power_in"))
      (node (ref "DOWN3") (pin "7") (pinfunction "GND_7") (pintype "power_in"))
      (node (ref "DOWN3") (pin "G1") (pinfunction "HAND1_G1") (pintype "passive"))
      (node (ref "DOWN3") (pin "G2") (pinfunction "HAND2_G2") (pintype "passive"))
      (node (ref "DOWN4") (pin "4") (pinfunction "GND_4") (pintype "power_in"))
      (node (ref "DOWN4") (pin "7") (pinfunction "GND_7") (pintype "power_in"))
      (node (ref "DOWN4") (pin "G1") (pinfunction "HAND1_G1") (pintype "passive"))
      (node (ref "DOWN4") (pin "G2") (pinfunction "HAND2_G2") (pintype "passive"))
      (node (ref "R1") (pin "2") (pinfunction "2_2") (pintype "passive"))
      (node (ref "R10") (pin "1") (pinfunction "1_1") (pintype "passive"))
      (node (ref "R11") (pin "1") (pinfunction "1_1") (pintype "passive"))
      (node (ref "R12") (pin "1") (pinfunction "1_1") (pintype "passive"))
      (node (ref "R13") (pin "1") (pinfunction "1_1") (pintype "passive"))
      (node (ref "R24") (pin "2") (pinfunction "2_2") (pintype "passive"))
      (node (ref "R25") (pin "2") (pinfunction "2_2") (pintype "passive"))
      (node (ref "R26") (pin "2") (pinfunction "2_2") (pintype "passive"))
      (node (ref "R27") (pin "2") (pinfunction "2_2") (pintype "passive"))
      (node (ref "R28") (pin "2") (pinfunction "2_2") (pintype "passive"))
      (node (ref "R29") (pin "2") (pinfunction "2_2") (pintype "passive"))
      (node (ref "R3") (pin "2") (pinfunction "2_2") (pintype "passive"))
      (node (ref "R4") (pin "2") (pinfunction "2_2") (pintype "passive"))
      (node (ref "R7") (pin "1") (pinfunction "1_1") (pintype "passive"))
      (node (ref "R9") (pin "2") (pinfunction "2_2") (pintype "passive"))
      (node (ref "U1") (pin "11") (pinfunction "PAD_11") (pintype "passive"))
      (node (ref "U1") (pin "9") (pinfunction "GND_9") (pintype "passive"))
      (node (ref "U10") (pin "6") (pinfunction "GND_6") (pintype "passive"))
      (node (ref "U2") (pin "11") (pinfunction "PAD_11") (pintype "passive"))
      (node (ref "U2") (pin "9") (pinfunction "GND_9") (pintype "passive"))
      (node (ref "U3") (pin "11") (pinfunction "PAD_11") (pintype "passive"))
      (node (ref "U3") (pin "9") (pinfunction "GND_9") (pintype "passive"))
      (node (ref "U4") (pin "2") (pinfunction "GND_2") (pintype "passive"))
      (node (ref "U5") (pin "11") (pinfunction "PAD_11") (pintype "passive"))
      (node (ref "U5") (pin "9") (pinfunction "GND_9") (pintype "passive"))
      (node (ref "U6") (pin "11") (pinfunction "GND_11") (pintype "passive"))
      (node (ref "U6") (pin "18") (pinfunction "GND_18") (pintype "passive"))
      (node (ref "U6") (pin "26") (pinfunction "GND_26") (pintype "passive"))
      (node (ref "U6") (pin "33") (pinfunction "GND_33") (pintype "passive"))
      (node (ref "U6") (pin "40") (pinfunction "GND_40") (pintype "passive"))
      (node (ref "U6") (pin "67") (pinfunction "GND_67") (pintype "passive"))
      (node (ref "U6") (pin "G1") (pinfunction "G1_G1") (pintype "passive"))
      (node (ref "U7") (pin "11") (pinfunction "PAD_11") (pintype "passive"))
      (node (ref "U7") (pin "9") (pinfunction "GND_9") (pintype "passive"))
      (node (ref "U8") (pin "4") (pinfunction "VSS_4") (pintype "passive"))
      (node (ref "U9") (pin "6") (pinfunction "GND_6") (pintype "passive"))
      (node (ref "USB1") (pin "1") (pinfunction "SH1_1") (pintype "passive"))
      (node (ref "USB1") (pin "2") (pinfunction "SH2_2") (pintype "passive"))
      (node (ref "USB1") (pin "3") (pinfunction "SH3_3") (pintype "passive"))
      (node (ref "USB1") (pin "4") (pinfunction "SH4_4") (pintype "passive"))
      (node (ref "USB1") (pin "A1") (pinfunction "GND_A1") (pintype "passive"))
      (node (ref "USB1") (pin "A12") (pinfunction "GND_A12") (pintype "passive"))
      (node (ref "USB1") (pin "B1") (pinfunction "GND_B1") (pintype "passive"))
      (node (ref "USB1") (pin "B12") (pinfunction "GND_B12") (pintype "passive"))
      (node (ref "USB2") (pin "A12") (pinfunction "GND_1_A12") (pintype "passive"))
      (node (ref "USB2") (pin "B12") (pinfunction "GND_2_B12") (pintype "passive"))
      (node (ref "USB2") (pin "MH1") (pinfunction "MH1_MH1") (pintype "passive"))
      (node (ref "USB2") (pin "MH2") (pinfunction "MH2_MH2") (pintype "passive"))
      (node (ref "USB2") (pin "MH3") (pinfunction "MH3_MH3") (pintype "passive"))
      (node (ref "USB2") (pin "MH4") (pinfunction "MH4_MH4") (pintype "passive"))
    )
    (net (code "60") (name "Net-(D2-PadK)") (class "Default")
      (node (ref "D2") (pin "K") (pinfunction "K_K") (pintype "passive"))
      (node (ref "R10") (pin "2") (pinfunction "2_2") (pintype "passive"))
    )
    (net (code "61") (name "Net-(D3-PadK)") (class "Default")
      (node (ref "D3") (pin "K") (pinfunction "K_K") (pintype "passive"))
      (node (ref "R11") (pin "2") (pinfunction "2_2") (pintype "passive"))
    )
    (net (code "62") (name "Net-(D4-PadK)") (class "Default")
      (node (ref "D4") (pin "K") (pinfunction "K_K") (pintype "passive"))
      (node (ref "R12") (pin "2") (pinfunction "2_2") (pintype "passive"))
    )
    (net (code "63") (name "Net-(D5-PadK)") (class "Default")
      (node (ref "D5") (pin "K") (pinfunction "K_K") (pintype "passive"))
      (node (ref "R13") (pin "2") (pinfunction "2_2") (pintype "passive"))
    )
    (net (code "64") (name "Net-(DOWN1-TXN)") (class "Default")
      (node (ref "C38") (pin "2") (pinfunction "2_2") (pintype "passive"))
      (node (ref "DOWN1") (pin "8") (pinfunction "TXN_8") (pintype "passive"))
    )
    (net (code "65") (name "Net-(DOWN1-TXP)") (class "Default")
      (node (ref "C39") (pin "2") (pinfunction "2_2") (pintype "passive"))
      (node (ref "DOWN1") (pin "9") (pinfunction "TXP_9") (pintype "passive"))
    )
    (net (code "66") (name "Net-(DOWN2-TXN)") (class "Default")
      (node (ref "C40") (pin "2") (pinfunction "2_2") (pintype "passive"))
      (node (ref "DOWN2") (pin "8") (pinfunction "TXN_8") (pintype "passive"))
    )
    (net (code "67") (name "Net-(DOWN2-TXP)") (class "Default")
      (node (ref "C41") (pin "2") (pinfunction "2_2") (pintype "passive"))
      (node (ref "DOWN2") (pin "9") (pinfunction "TXP_9") (pintype "passive"))
    )
    (net (code "68") (name "Net-(DOWN3-TXN)") (class "Default")
      (node (ref "C42") (pin "2") (pinfunction "2_2") (pintype "passive"))
      (node (ref "DOWN3") (pin "8") (pinfunction "TXN_8") (pintype "passive"))
    )
    (net (code "69") (name "Net-(DOWN3-TXP)") (class "Default")
      (node (ref "C43") (pin "2") (pinfunction "2_2") (pintype "passive"))
      (node (ref "DOWN3") (pin "9") (pinfunction "TXP_9") (pintype "passive"))
    )
    (net (code "70") (name "Net-(DOWN4-TXN)") (class "Default")
      (node (ref "C44") (pin "2") (pinfunction "2_2") (pintype "passive"))
      (node (ref "DOWN4") (pin "8") (pinfunction "TXN_8") (pintype "passive"))
    )
    (net (code "71") (name "Net-(DOWN4-TXP)") (class "Default")
      (node (ref "C45") (pin "2") (pinfunction "2_2") (pintype "passive"))
      (node (ref "DOWN4") (pin "9") (pinfunction "TXP_9") (pintype "passive"))
    )
    (net (code "72") (name "Net-(F1-Pad2)") (class "Default")
      (node (ref "F1") (pin "2") (pinfunction "2_2") (pintype "passive"))
      (node (ref "LB3") (pin "2") (pinfunction "2_2") (pintype "passive"))
    )
    (net (code "73") (name "Net-(U4-FB)") (class "Default")
      (node (ref "C32") (pin "1") (pinfunction "1_1") (pintype "passive"))
      (node (ref "R8") (pin "2") (pinfunction "2_2") (pintype "passive"))
      (node (ref "R9") (pin "1") (pinfunction "1_1") (pintype "passive"))
      (node (ref "U4") (pin "5") (pinfunction "FB_5") (pintype "passive"))
    )
    (net (code "74") (name "Net-(U4-LX)") (class "Default")
      (node (ref "LB4") (pin "1") (pinfunction "1_1") (pintype "passive"))
      (node (ref "U4") (pin "3") (pinfunction "LX_3") (pintype "passive"))
    )
    (net (code "75") (name "Net-(U8-~{HOLD})") (class "Default")
      (node (ref "R15") (pin "1") (pinfunction "1_1") (pintype "passive"))
      (node (ref "U8") (pin "7") (pinfunction "~{HOLD}_7") (pintype "passive"))
    )
    (net (code "76") (name "Net-(U8-~{WP})") (class "Default")
      (node (ref "R14") (pin "2") (pinfunction "2_2") (pintype "passive"))
      (node (ref "U8") (pin "3") (pinfunction "~{WP}_3") (pintype "passive"))
    )
    (net (code "77") (name "VAUX") (class "Default")
      (node (ref "C2") (pin "1") (pinfunction "1_1") (pintype "passive"))
      (node (ref "C4") (pin "2") (pinfunction "2_2") (pintype "passive"))
      (node (ref "D1") (pin "1") (pinfunction "A_1") (pintype "passive"))
      (node (ref "LB5") (pin "2") (pinfunction "2_2") (pintype "passive"))
      (node (ref "R1") (pin "1") (pinfunction "1_1") (pintype "passive"))
      (node (ref "R2") (pin "2") (pinfunction "2_2") (pintype "passive"))
    )
    (net (code "78") (name "VCC") (class "Default")
      (node (ref "C14") (pin "1") (pinfunction "1_1") (pintype "passive"))
      (node (ref "C17") (pin "2") (pinfunction "2_2") (pintype "passive"))
      (node (ref "C30") (pin "1") (pinfunction "1_1") (pintype "passive"))
      (node (ref "D1") (pin "2") (pinfunction "K_2") (pintype "passive"))
      (node (ref "Q1") (pin "2") (pinfunction "SOURCE_2") (pintype "passive"))
      (node (ref "R5") (pin "2") (pinfunction "2_2") (pintype "passive"))
      (node (ref "U1") (pin "2") (pinfunction "VCC_2") (pintype "passive"))
      (node (ref "U10") (pin "7") (pinfunction "IN_7") (pintype "passive"))
      (node (ref "U4") (pin "1") (pinfunction "EN_1") (pintype "passive"))
      (node (ref "U4") (pin "4") (pinfunction "VIN_4") (pintype "passive"))
      (node (ref "U6") (pin "86") (pinfunction "V5_LDO_86") (pintype "passive"))
      (node (ref "U9") (pin "7") (pinfunction "IN_7") (pintype "passive"))
    )
    (net (code "79") (name "VD12") (class "Default")
      (node (ref "C11") (pin "2") (pinfunction "2_2") (pintype "passive"))
      (node (ref "C21") (pin "2") (pinfunction "2_2") (pintype "passive"))
      (node (ref "C22") (pin "2") (pinfunction "2_2") (pintype "passive"))
      (node (ref "C23") (pin "2") (pinfunction "2_2") (pintype "passive"))
      (node (ref "C24") (pin "2") (pinfunction "2_2") (pintype "passive"))
      (node (ref "C31") (pin "1") (pinfunction "1_1") (pintype "passive"))
      (node (ref "C32") (pin "2") (pinfunction "2_2") (pintype "passive"))
      (node (ref "C33") (pin "2") (pinfunction "2_2") (pintype "passive"))
      (node (ref "C9") (pin "2") (pinfunction "2_2") (pintype "passive"))
      (node (ref "LB4") (pin "2") (pinfunction "2_2") (pintype "passive"))
      (node (ref "R8") (pin "1") (pinfunction "1_1") (pintype "passive"))
      (node (ref "U6") (pin "14") (pinfunction "VD12_14") (pintype "passive"))
      (node (ref "U6") (pin "15") (pinfunction "VD12_15") (pintype "passive"))
      (node (ref "U6") (pin "21") (pinfunction "VD12_21") (pintype "passive"))
      (node (ref "U6") (pin "23") (pinfunction "VD12_23") (pintype "passive"))
      (node (ref "U6") (pin "29") (pinfunction "VD12_29") (pintype "passive"))
      (node (ref "U6") (pin "30") (pinfunction "VD12_30") (pintype "passive"))
      (node (ref "U6") (pin "36") (pinfunction "VD12_36") (pintype "passive"))
      (node (ref "U6") (pin "37") (pinfunction "VD12_37") (pintype "passive"))
      (node (ref "U6") (pin "43") (pinfunction "VD12_43") (pintype "passive"))
      (node (ref "U6") (pin "44") (pinfunction "DVDD12_44") (pintype "passive"))
      (node (ref "U6") (pin "49") (pinfunction "DVDD12_49") (pintype "passive"))
      (node (ref "U6") (pin "57") (pinfunction "DVDD12_57") (pintype "passive"))
      (node (ref "U6") (pin "75") (pinfunction "DVDD12_75") (pintype "passive"))
    )
    (net (code "80") (name "VD33") (class "Default")
      (node (ref "C15") (pin "1") (pinfunction "1_1") (pintype "passive"))
      (node (ref "C20") (pin "2") (pinfunction "2_2") (pintype "passive"))
      (node (ref "R14") (pin "1") (pinfunction "1_1") (pintype "passive"))
      (node (ref "R15") (pin "2") (pinfunction "2_2") (pintype "passive"))
      (node (ref "R16") (pin "1") (pinfunction "1_1") (pintype "passive"))
      (node (ref "R17") (pin "1") (pinfunction "1_1") (pintype "passive"))
      (node (ref "R18") (pin "1") (pinfunction "1_1") (pintype "passive"))
      (node (ref "R19") (pin "1") (pinfunction "1_1") (pintype "passive"))
      (node (ref "R20") (pin "1") (pinfunction "1_1") (pintype "passive"))
      (node (ref "R21") (pin "1") (pinfunction "1_1") (pintype "passive"))
      (node (ref "R22") (pin "1") (pinfunction "1_1") (pintype "passive"))
      (node (ref "R23") (pin "1") (pinfunction "1_1") (pintype "passive"))
      (node (ref "U6") (pin "58") (pinfunction "DVDD_58") (pintype "passive"))
      (node (ref "U6") (pin "63") (pinfunction "AVDD_63") (pintype "passive"))
      (node (ref "U6") (pin "66") (pinfunction "AVDD_66") (pintype "passive"))
      (node (ref "U6") (pin "70") (pinfunction "AVDD_70") (pintype "passive"))
      (node (ref "U6") (pin "73") (pinfunction "DVDD_73") (pintype "passive"))
      (node (ref "U6") (pin "85") (pinfunction "V33_OUT_85") (pintype "passive"))
      (node (ref "U8") (pin "8") (pinfunction "VCC_8") (pintype "passive"))
    )
    (net (code "81") (name "VDP1") (class "Default")
      (node (ref "C12") (pin "1") (pinfunction "1_1") (pintype "passive"))
      (node (ref "C13") (pin "2") (pinfunction "2_2") (pintype "passive"))
      (node (ref "DOWN1") (pin "1") (pinfunction "VCC_1") (pintype "power_in"))
      (node (ref "U2") (pin "2") (pinfunction "VCC_2") (pintype "passive"))
      (node (ref "U9") (pin "8") (pinfunction "OUTA_8") (pintype "passive"))
    )
    (net (code "82") (name "VDP2") (class "Default")
      (node (ref "C25") (pin "1") (pinfunction "1_1") (pintype "passive"))
      (node (ref "C26") (pin "2") (pinfunction "2_2") (pintype "passive"))
      (node (ref "DOWN2") (pin "1") (pinfunction "VCC_1") (pintype "power_in"))
      (node (ref "U3") (pin "2") (pinfunction "VCC_2") (pintype "passive"))
      (node (ref "U9") (pin "5") (pinfunction "OUTB_5") (pintype "passive"))
    )
    (net (code "83") (name "VDP3") (class "Default")
      (node (ref "C34") (pin "1") (pinfunction "1_1") (pintype "passive"))
      (node (ref "C35") (pin "2") (pinfunction "2_2") (pintype "passive"))
      (node (ref "DOWN3") (pin "1") (pinfunction "VCC_1") (pintype "power_in"))
      (node (ref "U10") (pin "8") (pinfunction "OUTA_8") (pintype "passive"))
      (node (ref "U5") (pin "2") (pinfunction "VCC_2") (pintype "passive"))
    )
    (net (code "84") (name "VDP4") (class "Default")
      (node (ref "C36") (pin "1") (pinfunction "1_1") (pintype "passive"))
      (node (ref "C37") (pin "2") (pinfunction "2_2") (pintype "passive"))
      (node (ref "DOWN4") (pin "1") (pinfunction "VCC_1") (pintype "power_in"))
      (node (ref "U10") (pin "5") (pinfunction "OUTB_5") (pintype "passive"))
      (node (ref "U7") (pin "2") (pinfunction "VCC_2") (pintype "passive"))
    )
    (net (code "85") (name "VMAIN") (class "Default")
      (node (ref "C1") (pin "1") (pinfunction "1_1") (pintype "passive"))
      (node (ref "C3") (pin "2") (pinfunction "2_2") (pintype "passive"))
      (node (ref "F1") (pin "1") (pinfunction "1_1") (pintype "passive"))
      (node (ref "Q1") (pin "3") (pinfunction "DRAIN_3") (pintype "passive"))
      (node (ref "U6") (pin "55") (pinfunction "VBUS_55") (pintype "passive"))
    )
    (net (code "86") (name "unconnected-(U1-NC-Pad3)") (class "Default")
      (node (ref "U1") (pin "3") (pinfunction "NC_3") (pintype "passive+no_connect"))
    )
    (net (code "87") (name "unconnected-(U1-NC-Pad8)") (class "Default")
      (node (ref "U1") (pin "8") (pinfunction "NC_8") (pintype "passive+no_connect"))
    )
    (net (code "88") (name "unconnected-(U2-NC-Pad3)") (class "Default")
      (node (ref "U2") (pin "3") (pinfunction "NC_3") (pintype "passive+no_connect"))
    )
    (net (code "89") (name "unconnected-(U2-NC-Pad8)") (class "Default")
      (node (ref "U2") (pin "8") (pinfunction "NC_8") (pintype "passive+no_connect"))
    )
    (net (code "90") (name "unconnected-(U3-NC-Pad3)") (class "Default")
      (node (ref "U3") (pin "3") (pinfunction "NC_3") (pintype "passive+no_connect"))
    )
    (net (code "91") (name "unconnected-(U3-NC-Pad8)") (class "Default")
      (node (ref "U3") (pin "8") (pinfunction "NC_8") (pintype "passive+no_connect"))
    )
    (net (code "92") (name "unconnected-(U5-NC-Pad3)") (class "Default")
      (node (ref "U5") (pin "3") (pinfunction "NC_3") (pintype "passive+no_connect"))
    )
    (net (code "93") (name "unconnected-(U5-NC-Pad8)") (class "Default")
      (node (ref "U5") (pin "8") (pinfunction "NC_8") (pintype "passive+no_connect"))
    )
    (net (code "94") (name "unconnected-(U6-NC-Pad4)") (class "Default")
      (node (ref "U6") (pin "4") (pinfunction "NC_4") (pintype "passive+no_connect"))
    )
    (net (code "95") (name "unconnected-(U6-NC-Pad5)") (class "Default")
      (node (ref "U6") (pin "5") (pinfunction "NC_5") (pintype "passive+no_connect"))
    )
    (net (code "96") (name "unconnected-(U6-NC-Pad8)") (class "Default")
      (node (ref "U6") (pin "8") (pinfunction "NC_8") (pintype "passive+no_connect"))
    )
    (net (code "97") (name "unconnected-(U6-NC-Pad22)") (class "Default")
      (node (ref "U6") (pin "22") (pinfunction "NC_22") (pintype "passive"))
    )
    (net (code "98") (name "unconnected-(U6-PAMBER1-Pad52)") (class "Default")
      (node (ref "U6") (pin "52") (pinfunction "PAMBER1_52") (pintype "passive+no_connect"))
    )
    (net (code "99") (name "unconnected-(U6-PAMBER2-Pad87)") (class "Default")
      (node (ref "U6") (pin "87") (pinfunction "PAMBER2_87") (pintype "passive+no_connect"))
    )
    (net (code "100") (name "unconnected-(U6-PAMBER3-Pad56)") (class "Default")
      (node (ref "U6") (pin "56") (pinfunction "PAMBER3_56") (pintype "passive+no_connect"))
    )
    (net (code "101") (name "unconnected-(U6-PAMBER4-Pad1)") (class "Default")
      (node (ref "U6") (pin "1") (pinfunction "PAMBER4_1") (pintype "passive+no_connect"))
    )
    (net (code "102") (name "unconnected-(U6-TEST-Pad76)") (class "Default")
      (node (ref "U6") (pin "76") (pinfunction "TEST_76") (pintype "passive+no_connect"))
    )
    (net (code "103") (name "unconnected-(U7-NC-Pad3)") (class "Default")
      (node (ref "U7") (pin "3") (pinfunction "NC_3") (pintype "passive+no_connect"))
    )
    (net (code "104") (name "unconnected-(U7-NC-Pad8)") (class "Default")
      (node (ref "U7") (pin "8") (pinfunction "NC_8") (pintype "passive+no_connect"))
    )
    (net (code "105") (name "unconnected-(USB1-SBU1-PadA8)") (class "Default")
      (node (ref "USB1") (pin "A8") (pinfunction "SBU1_A8") (pintype "passive+no_connect"))
    )
    (net (code "106") (name "unconnected-(USB1-SBU2-PadB8)") (class "Default")
      (node (ref "USB1") (pin "B8") (pinfunction "SBU2_B8") (pintype "passive+no_connect"))
    )
    (net (code "107") (name "unconnected-(USB2-CC1-PadA5)") (class "Default")
      (node (ref "USB2") (pin "A5") (pinfunction "CC1_A5") (pintype "passive+no_connect"))
    )
    (net (code "108") (name "unconnected-(USB2-CC2-PadB5)") (class "Default")
      (node (ref "USB2") (pin "B5") (pinfunction "CC2_B5") (pintype "passive+no_connect"))
    )
  )
)
